# arduino-nano.net
KiCad netlist of a schematic drawn in Altium Designer
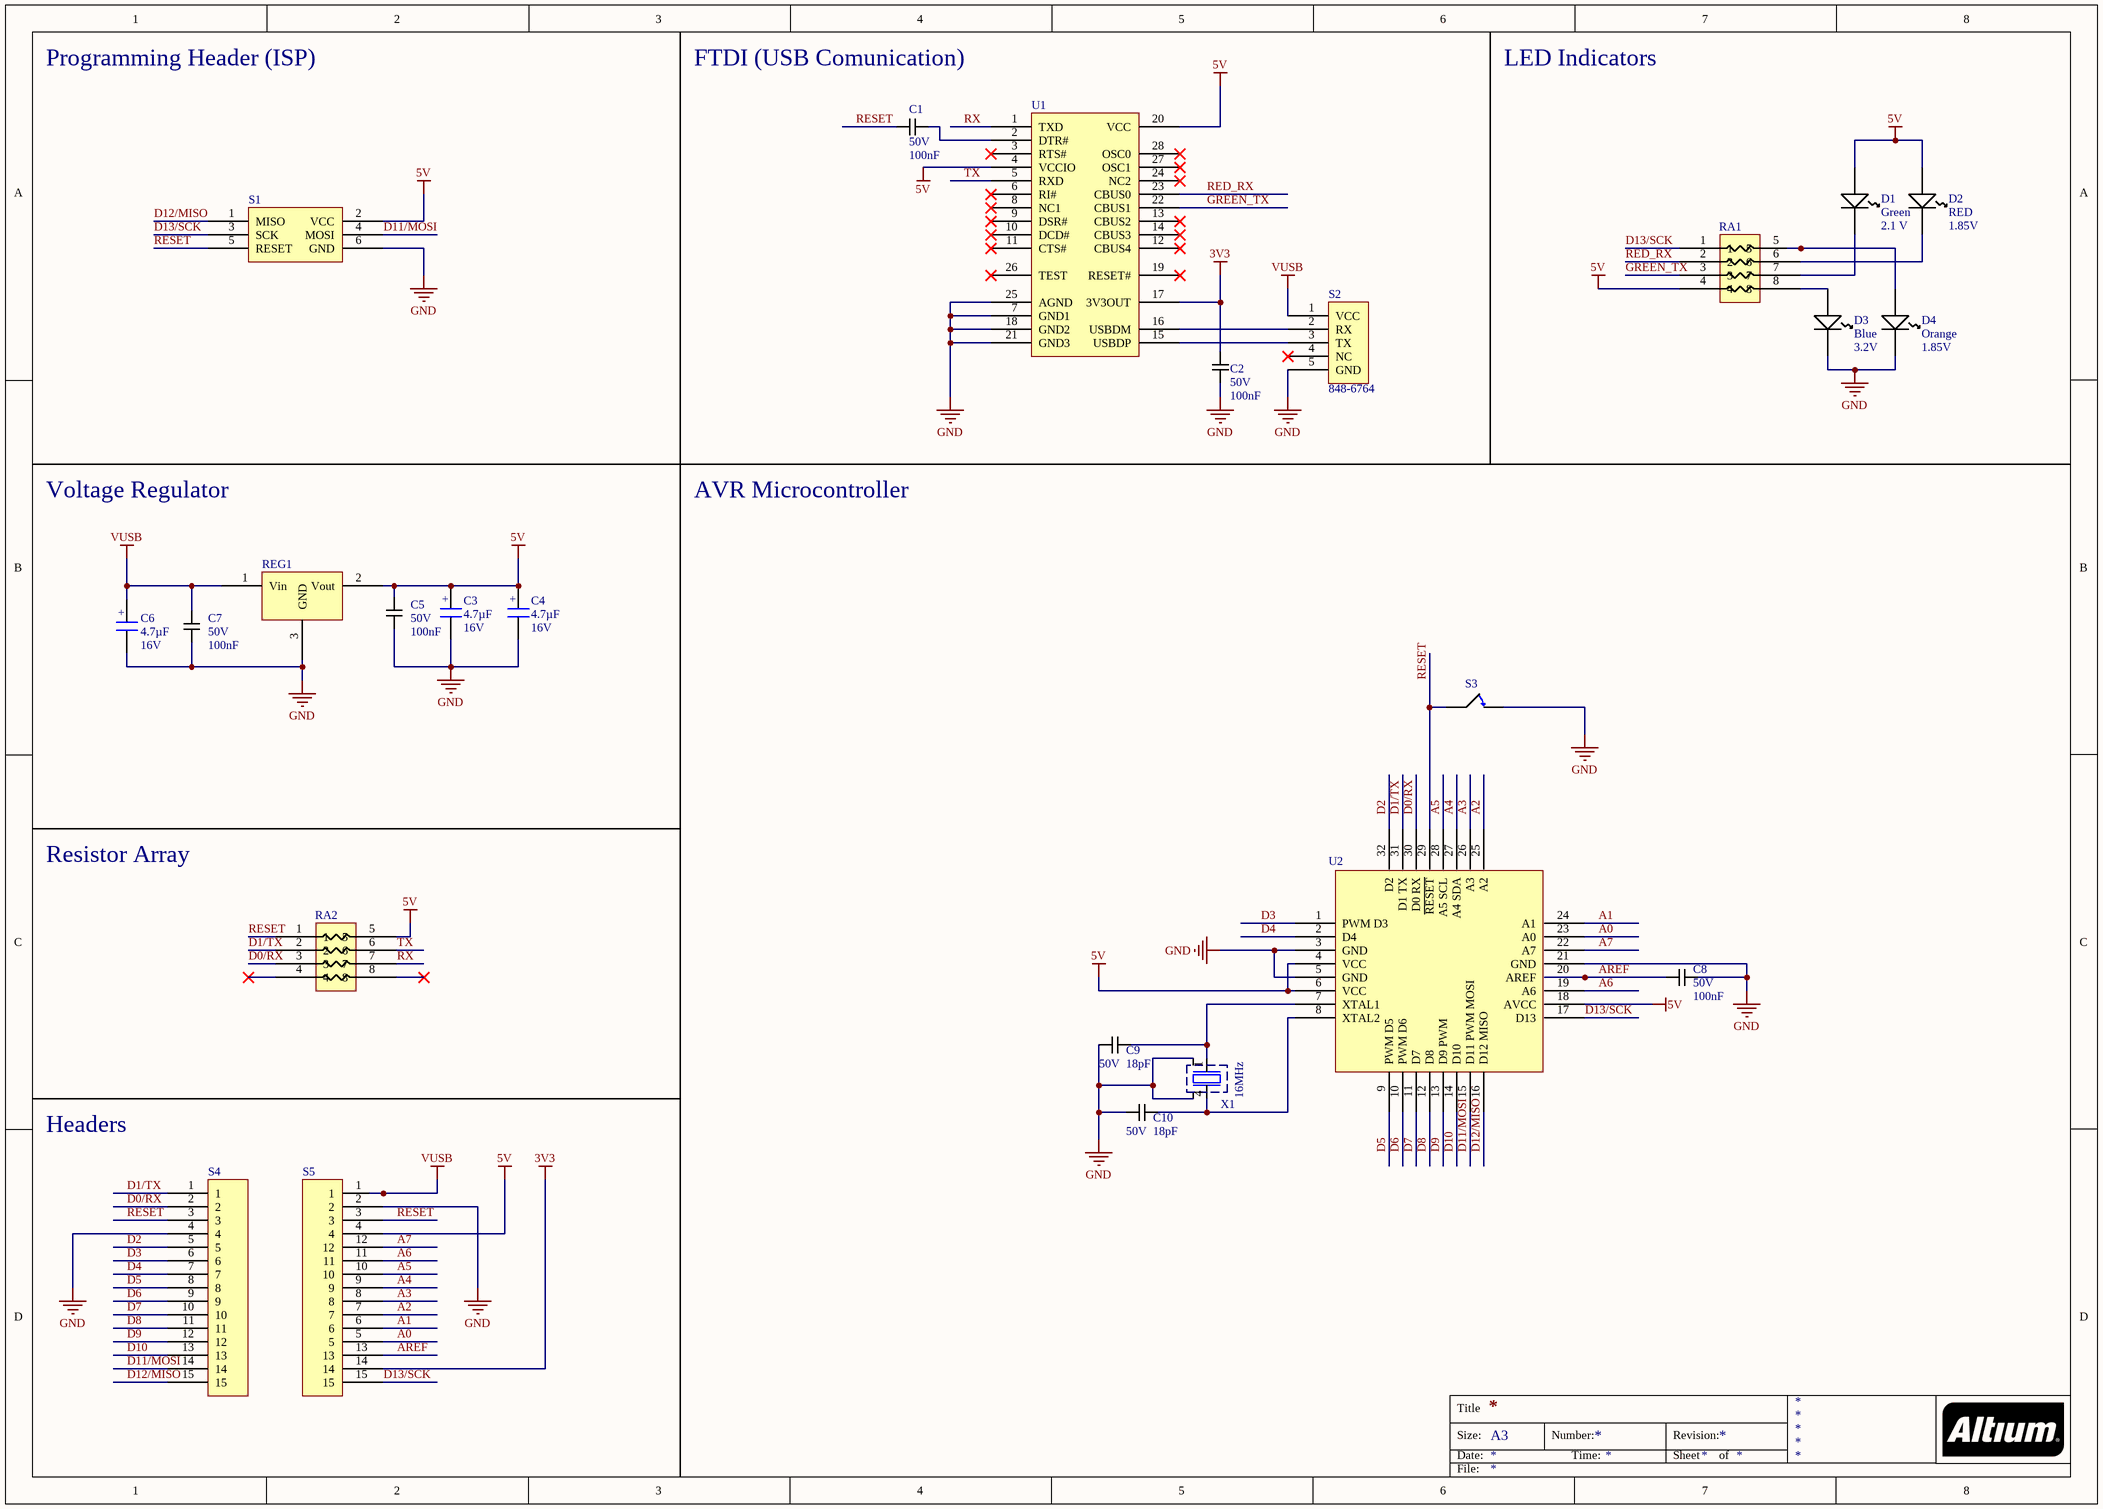
[diagram p0: arduino-nano.SchDoc]

(export (version "E")
  (design (tool "Eeschema 10.0.6"))
  (components
    (comp (ref "C1")
      (value "100nF Ceramic Multilayer Capacitor_1")
      (footprint "CAPCP2012X09N")
      (description "AVX 0805 Standard 100nF Ceramic Multilayer Capacitor, 50 V dc X7R Dielectric ±10% SMD")
      (fields
        (field (name "MANUFACTURER") "AVX")
        (field (name "VOLTAGE") "50V")
        (field (name "CAPACITANCE") "100nF")
        (field (name "CREATOR") "Ritesh Kanjee")
      )
      (libsource (lib "RS Components - Capacitors") (part "100nF Ceramic Multilayer Capacitor_1"))
    )
    (comp (ref "C2")
      (value "100nF Ceramic Multilayer Capacitor_1")
      (footprint "CAPCP2012X09N")
      (description "AVX 0805 Standard 100nF Ceramic Multilayer Capacitor, 50 V dc X7R Dielectric ±10% SMD")
      (fields
        (field (name "MANUFACTURER") "AVX")
        (field (name "VOLTAGE") "50V")
        (field (name "CAPACITANCE") "100nF")
        (field (name "CREATOR") "Ritesh Kanjee")
      )
      (libsource (lib "RS Components - Capacitors") (part "100nF Ceramic Multilayer Capacitor_1"))
    )
    (comp (ref "C3")
      (value "4.7µF")
      (footprint "CASE A - 3216X18")
      (description "Capacitor,tantalum,SMT,16V,4.7uF,10%,A-case")
      (fields
        (field (name "TOLERANCE") "10%")
        (field (name "VOLTAGE") "16V")
        (field (name "Comment") "Capacitor SMT Tantalum")
        (field (name "PUBLISHER") "DPSS")
      )
      (libsource (lib "RS Components - Capacitors") (part "4.7µF Tant RS 496-3545"))
    )
    (comp (ref "C4")
      (value "4.7µF")
      (footprint "CASE A - 3216X18")
      (description "Capacitor,tantalum,SMT,16V,4.7uF,10%,A-case")
      (fields
        (field (name "TOLERANCE") "10%")
        (field (name "VOLTAGE") "16V")
        (field (name "Comment") "Capacitor SMT Tantalum")
        (field (name "PUBLISHER") "DPSS")
      )
      (libsource (lib "RS Components - Capacitors") (part "4.7µF Tant RS 496-3545"))
    )
    (comp (ref "C5")
      (value "100nF Ceramic Multilayer Capacitor_1")
      (footprint "CAPCP2012X09N")
      (description "AVX 0805 Standard 100nF Ceramic Multilayer Capacitor, 50 V dc X7R Dielectric ±10% SMD")
      (fields
        (field (name "MANUFACTURER") "AVX")
        (field (name "VOLTAGE") "50V")
        (field (name "CAPACITANCE") "100nF")
        (field (name "CREATOR") "Ritesh Kanjee")
      )
      (libsource (lib "RS Components - Capacitors") (part "100nF Ceramic Multilayer Capacitor_1"))
    )
    (comp (ref "C6")
      (value "4.7µF")
      (footprint "CASE A - 3216X18")
      (description "Capacitor,tantalum,SMT,16V,4.7uF,10%,A-case")
      (fields
        (field (name "TOLERANCE") "10%")
        (field (name "VOLTAGE") "16V")
        (field (name "Comment") "Capacitor SMT Tantalum")
        (field (name "PUBLISHER") "DPSS")
      )
      (libsource (lib "RS Components - Capacitors") (part "4.7µF Tant RS 496-3545"))
    )
    (comp (ref "C7")
      (value "100nF Ceramic Multilayer Capacitor_1")
      (footprint "CAPCP2012X09N")
      (description "AVX 0805 Standard 100nF Ceramic Multilayer Capacitor, 50 V dc X7R Dielectric ±10% SMD")
      (fields
        (field (name "MANUFACTURER") "AVX")
        (field (name "VOLTAGE") "50V")
        (field (name "CAPACITANCE") "100nF")
        (field (name "CREATOR") "Ritesh Kanjee")
      )
      (libsource (lib "RS Components - Capacitors") (part "100nF Ceramic Multilayer Capacitor_1"))
    )
    (comp (ref "C8")
      (value "100nF Ceramic Multilayer Capacitor_1")
      (footprint "CAPCP2012X09N")
      (description "AVX 0805 Standard 100nF Ceramic Multilayer Capacitor, 50 V dc X7R Dielectric ±10% SMD")
      (fields
        (field (name "MANUFACTURER") "AVX")
        (field (name "VOLTAGE") "50V")
        (field (name "CAPACITANCE") "100nF")
        (field (name "CREATOR") "Ritesh Kanjee")
      )
      (libsource (lib "RS Components - Capacitors") (part "100nF Ceramic Multilayer Capacitor_1"))
    )
    (comp (ref "C9")
      (value "C0805C180J5GACTU")
      (footprint "CAPCP2012X09N")
      (description "18pF Ceramic Multilayer Capacitor, 50 V dc C0G Dielectric ±5% SMD")
      (fields
        (field (name "MANUFACTURER") "Kemet")
        (field (name "VOLTAGE") "50V")
        (field (name "CAPACITANCE") "18pF")
        (field (name "CREATOR") "Ritesh Kanjee")
      )
      (libsource (lib "RS Components - Capacitors") (part "18pF Ceramic Multilayer Capacitor, 50 V dc C0G Dielectric ±5% SMD"))
    )
    (comp (ref "C10")
      (value "C0805C180J5GACTU")
      (footprint "CAPCP2012X09N")
      (description "18pF Ceramic Multilayer Capacitor, 50 V dc C0G Dielectric ±5% SMD")
      (fields
        (field (name "MANUFACTURER") "Kemet")
        (field (name "VOLTAGE") "50V")
        (field (name "CAPACITANCE") "18pF")
        (field (name "CREATOR") "Ritesh Kanjee")
      )
      (libsource (lib "RS Components - Capacitors") (part "18pF Ceramic Multilayer Capacitor, 50 V dc C0G Dielectric ±5% SMD"))
    )
    (comp (ref "D1")
      (value "Kingbright Green LED, 70 mcd 120 ° 0805")
      (footprint "LED1913X12NGREEN")
      (fields
        (field (name "MANUFACTURER") "KingBright")
        (field (name "MANUFACTURER PART NO.") "KP-2012MGC")
        (field (name "COLOR") "Green")
        (field (name "FORWARD VOLTAGE") "2.1 V")
        (field (name "CREATOR") "Ritesh Kanjee")
      )
      (libsource (lib "KingBright LEDs") (part "Kingbright Green LED, 70 mcd 120 ° 0805"))
    )
    (comp (ref "D2")
      (value "Kingbright Red LED, 100 mcd 120 ° 0805")
      (footprint "LED1913X12NRED")
      (fields
        (field (name "MANUFACTURER") "KingBright")
        (field (name "MANUFACTURER PART NO.") "KP-2012SRC-PRV")
        (field (name "COLOR") "RED")
        (field (name "FORWARD VOLTAGE") "1.85V")
        (field (name "CREATOR") "Ritesh Kanjee")
      )
      (libsource (lib "KingBright LEDs") (part "Kingbright Red LED, 100 mcd 120 ° 0805"))
    )
    (comp (ref "D3")
      (value "Kingbright Blue LED, 60 mcd 120 ° 0805")
      (footprint "LED1913X12NBLUE")
      (fields
        (field (name "MANUFACTURER") "KingBright")
        (field (name "MANUFACTURER PART NO.") "KP-2012PBC-A")
        (field (name "COLOR") "Blue")
        (field (name "FORWARD VOLTAGE") "3.2V")
        (field (name "CREATOR") "Ritesh Kanjee")
      )
      (libsource (lib "KingBright LEDs") (part "Kingbright Blue LED, 60 mcd 120 ° 0805"))
    )
    (comp (ref "D4")
      (value "Kingbright Orange LED, 200 mcd 120 ° 0805")
      (footprint "LED1913X12NYEL/ORANGE")
      (fields
        (field (name "MANUFACTURER") "KingBright")
        (field (name "MANUFACTURER PART NO.") "KP-2012SEC")
        (field (name "COLOR") "Orange")
        (field (name "FORWARD VOLTAGE") "1.85V")
        (field (name "CREATOR") "Ritesh Kanjee")
      )
      (libsource (lib "KingBright LEDs") (part "Kingbright Orange LED, 200 mcd 120 ° 0805"))
    )
    (comp (ref "RA1")
      (value "1k +- 5% SMT Resistor Array")
      (footprint "1206 RA")
      (description "1k +- 5% SMT Resistor Array 4 Res")
      (fields
        (field (name "MANUFACTURER") "Bourns")
        (field (name "MANUFACTURER PART NO.") "CAY16-102J4LF")
        (field (name "CREATOR") "R Kanjee")
      )
      (libsource (lib "Bourns  Resistor Arrays") (part "1k +- 5% SMT Resistor Array"))
    )
    (comp (ref "RA2")
      (value "1k +- 5% SMT Resistor Array")
      (footprint "1206 RA")
      (description "1k +- 5% SMT Resistor Array 4 Res")
      (fields
        (field (name "MANUFACTURER") "Bourns")
        (field (name "MANUFACTURER PART NO.") "CAY16-102J4LF")
        (field (name "CREATOR") "R Kanjee")
      )
      (libsource (lib "Bourns  Resistor Arrays") (part "1k +- 5% SMT Resistor Array"))
    )
    (comp (ref "REG1")
      (value "LM1117MP-5.0/NOPB, Low Dropout Voltage Regulator, 1.5A, 5 V ±1%, 4-Pin SOT-223")
      (footprint "SOT230P700X180-4N")
      (fields (field (name "MANUFACTURER") "Texas Instruments") (field (name "CREATED BY") "R Kanjee"))
      (libsource (lib "TI Low Dropout Voltage Regulator") (part "LM1117MP-5.0"))
    )
    (comp (ref "S1")
      (value "Programming Headers Dual Row")
      (footprint "ISP HEADER")
      (fields
        (field (name "MANUFACTURER") "FCI")
        (field (name "MANUFACTURER PART NO.") "68000-236HLF")
        (field (name "CREATED BY") "R Kanjee")
      )
      (libsource (lib "PCB Headers") (part "Programming ISP, Programming Headers Dual Row"))
    )
    (comp (ref "S2")
      (value "NewMolex Right Angle SMT Female Type B Micro USB Connector, 30 V ac, 1.8A")
      (footprint "MicroUSB")
      (fields
        (field (name "MANUFACTURER") "Molex")
        (field (name "MANUFACTURER PART NO.") "105017-0001")
        (field (name "RS STOCK NO") "848-6764")
        (field (name "CREATOR") "R Kanjee")
      )
      (libsource (lib "Molex Connectors") (part "Micro USB Connector, 30 V ac, 1.8A"))
    )
    (comp (ref "S3")
      (value "Tactile Switch SPST- NO 0.05A @24V")
      (footprint "Button8014X17N")
      (fields
        (field (name "MANUFACTURER") "Omron")
        (field (name "MANUFACTURER PART NO.") "B3F1000")
        (field (name "CREATOR") "R Kanjee")
      )
      (libsource (lib "Omron Tactile Switches") (part "Tactile Switch SPST- NO 0.05A @24V"))
    )
    (comp (ref "S4")
      (value "connector;str header;single row;.1 cont centers;.095 tail;gold or gtx;36 contact")
      (footprint "Header")
      (fields
        (field (name "MANUFACTURER") "FCI")
        (field (name "MANUFACTURER PART NO.") "68000-236HLF")
        (field (name "CREATED BY") "R Kanjee")
      )
      (libsource (lib "") (part "Single row; PCB headers_1"))
    )
    (comp (ref "S5")
      (value "connector;str header;single row;.1 cont centers;.095 tail;gold or gtx;36 contact")
      (footprint "Header")
      (fields
        (field (name "MANUFACTURER") "FCI")
        (field (name "MANUFACTURER PART NO.") "68000-236HLF")
        (field (name "CREATED BY") "R Kanjee")
      )
      (libsource (lib "PCB Headers") (part "Single row; PCB headers"))
    )
    (comp (ref "U1")
      (value "FT232RL, Universal Asynchronous Receiver & Transmitter 3MBd, 28-Pin, SSOP")
      (footprint "SOP65P780X200-28N")
      (fields
        (field (name "MANUFACTURER PART NO.") "FT232RL")
        (field (name "MANUFACTURER") "FTDI Chip")
        (field (name "CREATOR") "R Kanjee")
      )
      (libsource (lib "FTDI RS232toUSB") (part "FT232RL USB to UART, Universal Asynchronous Receiver & Transmitter 3MBd, 28-Pin, SSOP"))
    )
    (comp (ref "U2")
      (value "ATMEGA328P-AU")
      (footprint "TQFP80P900X900X120-32N")
      (description "Microchip ATMEGA328P-AU, 8bit AVR Microcontroller, 20MHz, 1 kB, 32 kB Flash, 32-Pin TQFP")
      (fields (field (name "CREATED BY") "Rajiv Bishwokarma"))
      (libsource (lib "Atmel-Microcontrollers") (part "ATMEGA328P-AU"))
    )
    (comp (ref "X1")
      (value "16MHz")
      (footprint "Aker S5C Crystal")
      (description "Aker S5C SMT Crystal")
      (fields
        (field (name "MANUFACTURER") "Aker")
        (field (name "MANUFACTURER PART #") "C5S-16.000-12-3030-X")
        (field (name "CREATOR") "R Kanjee")
      )
      (libsource (lib "Aker Crystals") (part "Aker  C5S-16.000-12-3030-X"))
    )
  )
  (nets
    (net (code "1") (name "/A0") (class "Default")
      (node (ref "S5") (pin "5") (pinfunction "5_5") (pintype "passive"))
      (node (ref "U2") (pin "23") (pinfunction "A0_23") (pintype "passive"))
    )
    (net (code "2") (name "/A1") (class "Default")
      (node (ref "S5") (pin "6") (pinfunction "6_6") (pintype "passive"))
      (node (ref "U2") (pin "24") (pinfunction "A1_24") (pintype "passive"))
    )
    (net (code "3") (name "/A2") (class "Default")
      (node (ref "S5") (pin "7") (pinfunction "7_7") (pintype "passive"))
      (node (ref "U2") (pin "25") (pinfunction "A2_25") (pintype "passive"))
    )
    (net (code "4") (name "/A3") (class "Default")
      (node (ref "S5") (pin "8") (pinfunction "8_8") (pintype "passive"))
      (node (ref "U2") (pin "26") (pinfunction "A3_26") (pintype "passive"))
    )
    (net (code "5") (name "/A4") (class "Default")
      (node (ref "S5") (pin "9") (pinfunction "9_9") (pintype "passive"))
      (node (ref "U2") (pin "27") (pinfunction "A4_SDA_27") (pintype "passive"))
    )
    (net (code "6") (name "/A5") (class "Default")
      (node (ref "S5") (pin "10") (pinfunction "10_10") (pintype "passive"))
      (node (ref "U2") (pin "28") (pinfunction "A5_SCL_28") (pintype "passive"))
    )
    (net (code "7") (name "/A6") (class "Default")
      (node (ref "S5") (pin "11") (pinfunction "11_11") (pintype "passive"))
      (node (ref "U2") (pin "19") (pinfunction "A6_19") (pintype "passive"))
    )
    (net (code "8") (name "/A7") (class "Default")
      (node (ref "S5") (pin "12") (pinfunction "12_12") (pintype "passive"))
      (node (ref "U2") (pin "22") (pinfunction "A7_22") (pintype "passive"))
    )
    (net (code "9") (name "/AREF") (class "Default")
      (node (ref "C8") (pin "1") (pinfunction "1_1") (pintype "passive"))
      (node (ref "S5") (pin "13") (pinfunction "13_13") (pintype "passive"))
      (node (ref "U2") (pin "20") (pinfunction "AREF_20") (pintype "passive"))
    )
    (net (code "10") (name "/D0{slash}RX") (class "Default")
      (node (ref "RA2") (pin "3") (pinfunction "3_3") (pintype "passive"))
      (node (ref "S4") (pin "2") (pinfunction "2_2") (pintype "passive"))
      (node (ref "U2") (pin "30") (pinfunction "D0_RX_30") (pintype "passive"))
    )
    (net (code "11") (name "/D1{slash}TX") (class "Default")
      (node (ref "RA2") (pin "2") (pinfunction "2_2") (pintype "passive"))
      (node (ref "S4") (pin "1") (pinfunction "1_1") (pintype "passive"))
      (node (ref "U2") (pin "31") (pinfunction "D1_TX_31") (pintype "passive"))
    )
    (net (code "12") (name "/D2") (class "Default")
      (node (ref "S4") (pin "5") (pinfunction "5_5") (pintype "passive"))
      (node (ref "U2") (pin "32") (pinfunction "D2_32") (pintype "passive"))
    )
    (net (code "13") (name "/D3") (class "Default")
      (node (ref "S4") (pin "6") (pinfunction "6_6") (pintype "passive"))
      (node (ref "U2") (pin "1") (pinfunction "PWM_D3_1") (pintype "passive"))
    )
    (net (code "14") (name "/D4") (class "Default")
      (node (ref "S4") (pin "7") (pinfunction "7_7") (pintype "passive"))
      (node (ref "U2") (pin "2") (pinfunction "D4_2") (pintype "passive"))
    )
    (net (code "15") (name "/D5") (class "Default")
      (node (ref "S4") (pin "8") (pinfunction "8_8") (pintype "passive"))
      (node (ref "U2") (pin "9") (pinfunction "PWM_D5_9") (pintype "passive"))
    )
    (net (code "16") (name "/D6") (class "Default")
      (node (ref "S4") (pin "9") (pinfunction "9_9") (pintype "passive"))
      (node (ref "U2") (pin "10") (pinfunction "PWM_D6_10") (pintype "passive"))
    )
    (net (code "17") (name "/D7") (class "Default")
      (node (ref "S4") (pin "10") (pinfunction "10_10") (pintype "passive"))
      (node (ref "U2") (pin "11") (pinfunction "D7_11") (pintype "passive"))
    )
    (net (code "18") (name "/D8") (class "Default")
      (node (ref "S4") (pin "11") (pinfunction "11_11") (pintype "passive"))
      (node (ref "U2") (pin "12") (pinfunction "D8_12") (pintype "passive"))
    )
    (net (code "19") (name "/D9") (class "Default")
      (node (ref "S4") (pin "12") (pinfunction "12_12") (pintype "passive"))
      (node (ref "U2") (pin "13") (pinfunction "D9_PWM_13") (pintype "passive"))
    )
    (net (code "20") (name "/D10") (class "Default")
      (node (ref "S4") (pin "13") (pinfunction "13_13") (pintype "passive"))
      (node (ref "U2") (pin "14") (pinfunction "D10_14") (pintype "passive"))
    )
    (net (code "21") (name "/D11{slash}MOSI") (class "Default")
      (node (ref "S1") (pin "4") (pinfunction "MOSI_4") (pintype "passive"))
      (node (ref "S4") (pin "14") (pinfunction "14_14") (pintype "passive"))
      (node (ref "U2") (pin "15") (pinfunction "D11_PWM_MOSI_15") (pintype "passive"))
    )
    (net (code "22") (name "/D12{slash}MISO") (class "Default")
      (node (ref "S1") (pin "1") (pinfunction "MISO_1") (pintype "passive"))
      (node (ref "S4") (pin "15") (pinfunction "15_15") (pintype "passive"))
      (node (ref "U2") (pin "16") (pinfunction "D12_MISO_16") (pintype "passive"))
    )
    (net (code "23") (name "/D13{slash}SCK") (class "Default")
      (node (ref "RA1") (pin "1") (pinfunction "1_1") (pintype "passive"))
      (node (ref "S1") (pin "3") (pinfunction "SCK_3") (pintype "passive"))
      (node (ref "S5") (pin "15") (pinfunction "15_15") (pintype "passive"))
      (node (ref "U2") (pin "17") (pinfunction "D13_17") (pintype "passive"))
    )
    (net (code "24") (name "/GREEN_TX") (class "Default")
      (node (ref "RA1") (pin "3") (pinfunction "3_3") (pintype "passive"))
      (node (ref "U1") (pin "22") (pinfunction "CBUS1_22") (pintype "passive"))
    )
    (net (code "25") (name "/RED_RX") (class "Default")
      (node (ref "RA1") (pin "2") (pinfunction "2_2") (pintype "passive"))
      (node (ref "U1") (pin "23") (pinfunction "CBUS0_23") (pintype "passive"))
    )
    (net (code "26") (name "/RESET") (class "Default")
      (node (ref "C1") (pin "1") (pinfunction "1_1") (pintype "passive"))
      (node (ref "RA2") (pin "1") (pinfunction "1_1") (pintype "passive"))
      (node (ref "S1") (pin "5") (pinfunction "RESET_5") (pintype "passive"))
      (node (ref "S3") (pin "2") (pinfunction "2_2") (pintype "passive"))
      (node (ref "S4") (pin "3") (pinfunction "3_3") (pintype "passive"))
      (node (ref "S5") (pin "3") (pinfunction "3_3") (pintype "passive"))
      (node (ref "U2") (pin "29") (pinfunction "~{RESET}_29") (pintype "passive"))
    )
    (net (code "27") (name "/RX") (class "Default")
      (node (ref "RA2") (pin "7") (pinfunction "7_7") (pintype "passive"))
      (node (ref "U1") (pin "1") (pinfunction "TXD_1") (pintype "passive"))
    )
    (net (code "28") (name "/TX") (class "Default")
      (node (ref "RA2") (pin "6") (pinfunction "6_6") (pintype "passive"))
      (node (ref "U1") (pin "5") (pinfunction "RXD_5") (pintype "passive"))
    )
    (net (code "29") (name "3V3") (class "Default")
      (node (ref "C2") (pin "2") (pinfunction "2_2") (pintype "passive"))
      (node (ref "S5") (pin "14") (pinfunction "14_14") (pintype "passive"))
      (node (ref "U1") (pin "17") (pinfunction "3V3OUT_17") (pintype "passive"))
    )
    (net (code "30") (name "5V") (class "Default")
      (node (ref "C3") (pin "1") (pinfunction "1_1") (pintype "passive"))
      (node (ref "C4") (pin "1") (pinfunction "1_1") (pintype "passive"))
      (node (ref "C5") (pin "2") (pinfunction "2_2") (pintype "passive"))
      (node (ref "D1") (pin "1") (pinfunction "A_1") (pintype "passive"))
      (node (ref "D2") (pin "1") (pinfunction "A_1") (pintype "passive"))
      (node (ref "RA1") (pin "4") (pinfunction "4_4") (pintype "passive"))
      (node (ref "RA2") (pin "5") (pinfunction "5_5") (pintype "passive"))
      (node (ref "REG1") (pin "2") (pinfunction "Vout_2") (pintype "passive"))
      (node (ref "S1") (pin "2") (pinfunction "VCC_2") (pintype "passive"))
      (node (ref "S5") (pin "4") (pinfunction "4_4") (pintype "passive"))
      (node (ref "U1") (pin "20") (pinfunction "VCC_20") (pintype "passive"))
      (node (ref "U1") (pin "4") (pinfunction "VCCIO_4") (pintype "passive"))
      (node (ref "U2") (pin "18") (pinfunction "AVCC_18") (pintype "passive"))
      (node (ref "U2") (pin "4") (pinfunction "VCC_4") (pintype "passive"))
      (node (ref "U2") (pin "6") (pinfunction "VCC_6") (pintype "passive"))
    )
    (net (code "31") (name "GND") (class "Default")
      (node (ref "C10") (pin "2") (pinfunction "2_2") (pintype "passive"))
      (node (ref "C2") (pin "1") (pinfunction "1_1") (pintype "passive"))
      (node (ref "C3") (pin "2") (pinfunction "2_2") (pintype "passive"))
      (node (ref "C4") (pin "2") (pinfunction "2_2") (pintype "passive"))
      (node (ref "C5") (pin "1") (pinfunction "1_1") (pintype "passive"))
      (node (ref "C6") (pin "2") (pinfunction "2_2") (pintype "passive"))
      (node (ref "C7") (pin "1") (pinfunction "1_1") (pintype "passive"))
      (node (ref "C8") (pin "2") (pinfunction "2_2") (pintype "passive"))
      (node (ref "C9") (pin "2") (pinfunction "2_2") (pintype "passive"))
      (node (ref "D3") (pin "2") (pinfunction "K_2") (pintype "passive"))
      (node (ref "D4") (pin "2") (pinfunction "K_2") (pintype "passive"))
      (node (ref "REG1") (pin "3") (pinfunction "GND_3") (pintype "passive"))
      (node (ref "S1") (pin "6") (pinfunction "GND_6") (pintype "passive"))
      (node (ref "S2") (pin "5") (pinfunction "GND_5") (pintype "passive"))
      (node (ref "S3") (pin "1") (pinfunction "1_1") (pintype "passive"))
      (node (ref "S4") (pin "4") (pinfunction "4_4") (pintype "passive"))
      (node (ref "S5") (pin "2") (pinfunction "2_2") (pintype "passive"))
      (node (ref "U1") (pin "18") (pinfunction "GND2_18") (pintype "passive"))
      (node (ref "U1") (pin "21") (pinfunction "GND3_21") (pintype "passive"))
      (node (ref "U1") (pin "25") (pinfunction "AGND_25") (pintype "passive"))
      (node (ref "U1") (pin "7") (pinfunction "GND1_7") (pintype "passive"))
      (node (ref "U2") (pin "21") (pinfunction "GND_21") (pintype "passive"))
      (node (ref "U2") (pin "3") (pinfunction "GND_3") (pintype "passive"))
      (node (ref "U2") (pin "5") (pinfunction "GND_5") (pintype "passive"))
      (node (ref "X1") (pin "2") (pinfunction "Gnd_2") (pintype "power_in"))
      (node (ref "X1") (pin "3") (pinfunction "Gnd_3") (pintype "power_in"))
    )
    (net (code "32") (name "Net-(D1-K)") (class "Default")
      (node (ref "D1") (pin "2") (pinfunction "K_2") (pintype "passive"))
      (node (ref "RA1") (pin "7") (pinfunction "7_7") (pintype "passive"))
    )
    (net (code "33") (name "Net-(D2-K)") (class "Default")
      (node (ref "D2") (pin "2") (pinfunction "K_2") (pintype "passive"))
      (node (ref "RA1") (pin "6") (pinfunction "6_6") (pintype "passive"))
    )
    (net (code "34") (name "Net-(D3-A)") (class "Default")
      (node (ref "D3") (pin "1") (pinfunction "A_1") (pintype "passive"))
      (node (ref "RA1") (pin "8") (pinfunction "8_8") (pintype "passive"))
    )
    (net (code "35") (name "Net-(D4-A)") (class "Default")
      (node (ref "D4") (pin "1") (pinfunction "A_1") (pintype "passive"))
      (node (ref "RA1") (pin "5") (pinfunction "5_5") (pintype "passive"))
    )
    (net (code "36") (name "Net-(S2-RX)") (class "Default")
      (node (ref "S2") (pin "2") (pinfunction "RX_2") (pintype "passive"))
      (node (ref "U1") (pin "16") (pinfunction "USBDM_16") (pintype "passive"))
    )
    (net (code "37") (name "Net-(S2-TX)") (class "Default")
      (node (ref "S2") (pin "3") (pinfunction "TX_3") (pintype "passive"))
      (node (ref "U1") (pin "15") (pinfunction "USBDP_15") (pintype "passive"))
    )
    (net (code "38") (name "Net-(U1-DTR#)") (class "Default")
      (node (ref "C1") (pin "2") (pinfunction "2_2") (pintype "passive"))
      (node (ref "U1") (pin "2") (pinfunction "DTR#_2") (pintype "passive"))
    )
    (net (code "39") (name "Net-(U2-XTAL1)") (class "Default")
      (node (ref "C9") (pin "1") (pinfunction "1_1") (pintype "passive"))
      (node (ref "U2") (pin "7") (pinfunction "XTAL1_7") (pintype "passive"))
      (node (ref "X1") (pin "1") (pinfunction "1_1") (pintype "passive"))
    )
    (net (code "40") (name "Net-(U2-XTAL2)") (class "Default")
      (node (ref "C10") (pin "1") (pinfunction "1_1") (pintype "passive"))
      (node (ref "U2") (pin "8") (pinfunction "XTAL2_8") (pintype "passive"))
      (node (ref "X1") (pin "4") (pinfunction "4_4") (pintype "passive"))
    )
    (net (code "41") (name "VUSB") (class "Default")
      (node (ref "C6") (pin "1") (pinfunction "1_1") (pintype "passive"))
      (node (ref "C7") (pin "2") (pinfunction "2_2") (pintype "passive"))
      (node (ref "REG1") (pin "1") (pinfunction "Vin_1") (pintype "passive"))
      (node (ref "S2") (pin "1") (pinfunction "VCC_1") (pintype "passive"))
      (node (ref "S5") (pin "1") (pinfunction "1_1") (pintype "passive"))
    )
    (net (code "42") (name "unconnected-(RA2-Pad4)") (class "Default")
      (node (ref "RA2") (pin "4") (pinfunction "4_4") (pintype "passive+no_connect"))
    )
    (net (code "43") (name "unconnected-(RA2-Pad8)") (class "Default")
      (node (ref "RA2") (pin "8") (pinfunction "8_8") (pintype "passive+no_connect"))
    )
    (net (code "44") (name "unconnected-(S2-NC-Pad4)") (class "Default")
      (node (ref "S2") (pin "4") (pinfunction "NC_4") (pintype "passive+no_connect"))
    )
    (net (code "45") (name "unconnected-(U1-CBUS2-Pad13)") (class "Default")
      (node (ref "U1") (pin "13") (pinfunction "CBUS2_13") (pintype "passive+no_connect"))
    )
    (net (code "46") (name "unconnected-(U1-CBUS3-Pad14)") (class "Default")
      (node (ref "U1") (pin "14") (pinfunction "CBUS3_14") (pintype "passive+no_connect"))
    )
    (net (code "47") (name "unconnected-(U1-CBUS4-Pad12)") (class "Default")
      (node (ref "U1") (pin "12") (pinfunction "CBUS4_12") (pintype "passive+no_connect"))
    )
    (net (code "48") (name "unconnected-(U1-CTS#-Pad11)") (class "Default")
      (node (ref "U1") (pin "11") (pinfunction "CTS#_11") (pintype "passive+no_connect"))
    )
    (net (code "49") (name "unconnected-(U1-DCD#-Pad10)") (class "Default")
      (node (ref "U1") (pin "10") (pinfunction "DCD#_10") (pintype "passive+no_connect"))
    )
    (net (code "50") (name "unconnected-(U1-DSR#-Pad9)") (class "Default")
      (node (ref "U1") (pin "9") (pinfunction "DSR#_9") (pintype "passive+no_connect"))
    )
    (net (code "51") (name "unconnected-(U1-NC1-Pad8)") (class "Default")
      (node (ref "U1") (pin "8") (pinfunction "NC1_8") (pintype "passive+no_connect"))
    )
    (net (code "52") (name "unconnected-(U1-NC2-Pad24)") (class "Default")
      (node (ref "U1") (pin "24") (pinfunction "NC2_24") (pintype "passive+no_connect"))
    )
    (net (code "53") (name "unconnected-(U1-OSC0-Pad28)") (class "Default")
      (node (ref "U1") (pin "28") (pinfunction "OSC0_28") (pintype "passive+no_connect"))
    )
    (net (code "54") (name "unconnected-(U1-OSC1-Pad27)") (class "Default")
      (node (ref "U1") (pin "27") (pinfunction "OSC1_27") (pintype "passive+no_connect"))
    )
    (net (code "55") (name "unconnected-(U1-RESET#-Pad19)") (class "Default")
      (node (ref "U1") (pin "19") (pinfunction "RESET#_19") (pintype "passive+no_connect"))
    )
    (net (code "56") (name "unconnected-(U1-RI#-Pad6)") (class "Default")
      (node (ref "U1") (pin "6") (pinfunction "RI#_6") (pintype "passive+no_connect"))
    )
    (net (code "57") (name "unconnected-(U1-RTS#-Pad3)") (class "Default")
      (node (ref "U1") (pin "3") (pinfunction "RTS#_3") (pintype "passive+no_connect"))
    )
    (net (code "58") (name "unconnected-(U1-TEST-Pad26)") (class "Default")
      (node (ref "U1") (pin "26") (pinfunction "TEST_26") (pintype "passive+no_connect"))
    )
  )
)
